# Adaptador_ESP12.net
KiCad netlist of a schematic drawn in EAGLE
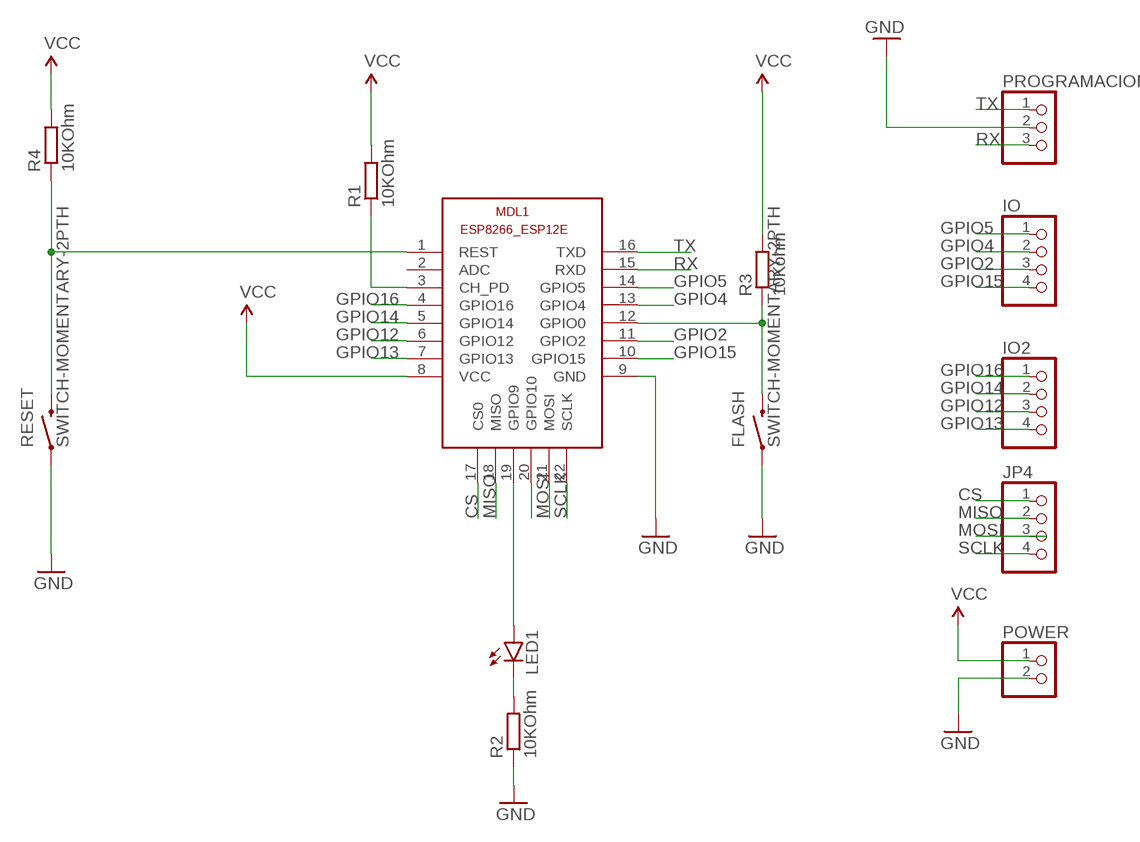
[diagram p0: schematic, sheet 1]

(export (version "E")
  (design (tool "Eeschema 10.0.6"))
  (components
    (comp (ref "FLASH")
      (value "SWITCH-MOMENTARY-2PTH")
      (footprint "eagle-import:TACTILE-PTH")
      (libsource (lib "eagle-import") (part "SWITCH-MOMENTARY-2PTH"))
    )
    (comp (ref "IO")
      (value "PINHD-1X4")
      (footprint "eagle-import:1X04")
      (libsource (lib "eagle-import") (part "PINHD-1X4"))
    )
    (comp (ref "IO2")
      (value "PINHD-1X4")
      (footprint "eagle-import:1X04")
      (libsource (lib "eagle-import") (part "PINHD-1X4"))
    )
    (comp (ref "JP4")
      (value "PINHD-1X4")
      (footprint "eagle-import:1X04")
      (libsource (lib "eagle-import") (part "PINHD-1X4"))
    )
    (comp (ref "LED1")
      (value "LED-3MM-NO_SILK")
      (footprint "eagle-import:LED3MM-NS")
      (libsource (lib "eagle-import") (part "LED-3MM-NO_SILK"))
    )
    (comp (ref "MDL1")
      (value "ESP8266-12EESP8266-ESP12E")
      (footprint "eagle-import:ESP8266-ESP12E")
      (libsource (lib "eagle-import") (part "ESP8266-12EESP8266-ESP12E"))
    )
    (comp (ref "POWER")
      (value "PINHD-1X2")
      (footprint "eagle-import:1X02")
      (libsource (lib "eagle-import") (part "PINHD-1X2"))
    )
    (comp (ref "PROGRAMACION")
      (value "PINHD-1X3")
      (footprint "eagle-import:1X03")
      (libsource (lib "eagle-import") (part "PINHD-1X3"))
    )
    (comp (ref "R1")
      (value "10KOhm")
      (footprint "eagle-import:0207_7")
      (libsource (lib "eagle-import") (part "R-EU_0207/7"))
    )
    (comp (ref "R2")
      (value "10KOhm")
      (footprint "eagle-import:0207_7")
      (libsource (lib "eagle-import") (part "R-EU_0207/7"))
    )
    (comp (ref "R3")
      (value "10Kohm")
      (footprint "eagle-import:0207_7")
      (libsource (lib "eagle-import") (part "R-EU_0207/7"))
    )
    (comp (ref "R4")
      (value "10KOhm")
      (footprint "eagle-import:0207_7")
      (libsource (lib "eagle-import") (part "R-EU_0207/7"))
    )
    (comp (ref "RESET")
      (value "SWITCH-MOMENTARY-2PTH")
      (footprint "eagle-import:TACTILE-PTH")
      (libsource (lib "eagle-import") (part "SWITCH-MOMENTARY-2PTH"))
    )
  )
  (nets
    (net (code "1") (name "/CS") (class "Default")
      (node (ref "JP4") (pin "1") (pinfunction "1_1") (pintype "passive"))
      (node (ref "MDL1") (pin "17") (pinfunction "CS0_17") (pintype "bidirectional"))
    )
    (net (code "2") (name "/GPIO2") (class "Default")
      (node (ref "IO") (pin "3") (pinfunction "3_3") (pintype "passive"))
      (node (ref "MDL1") (pin "11") (pinfunction "GPIO2_11") (pintype "bidirectional"))
    )
    (net (code "3") (name "/GPIO4") (class "Default")
      (node (ref "IO") (pin "2") (pinfunction "2_2") (pintype "passive"))
      (node (ref "MDL1") (pin "13") (pinfunction "GPIO4_13") (pintype "bidirectional"))
    )
    (net (code "4") (name "/GPIO5") (class "Default")
      (node (ref "IO") (pin "1") (pinfunction "1_1") (pintype "passive"))
      (node (ref "MDL1") (pin "14") (pinfunction "GPIO5_14") (pintype "bidirectional"))
    )
    (net (code "5") (name "/GPIO12") (class "Default")
      (node (ref "IO2") (pin "3") (pinfunction "3_3") (pintype "passive"))
      (node (ref "MDL1") (pin "6") (pinfunction "GPIO12_6") (pintype "bidirectional"))
    )
    (net (code "6") (name "/GPIO13") (class "Default")
      (node (ref "IO2") (pin "4") (pinfunction "4_4") (pintype "passive"))
      (node (ref "MDL1") (pin "7") (pinfunction "GPIO13_7") (pintype "bidirectional"))
    )
    (net (code "7") (name "/GPIO14") (class "Default")
      (node (ref "IO2") (pin "2") (pinfunction "2_2") (pintype "passive"))
      (node (ref "MDL1") (pin "5") (pinfunction "GPIO14_5") (pintype "bidirectional"))
    )
    (net (code "8") (name "/GPIO15") (class "Default")
      (node (ref "IO") (pin "4") (pinfunction "4_4") (pintype "passive"))
      (node (ref "MDL1") (pin "10") (pinfunction "GPIO15_10") (pintype "bidirectional"))
    )
    (net (code "9") (name "/GPIO16") (class "Default")
      (node (ref "IO2") (pin "1") (pinfunction "1_1") (pintype "passive"))
      (node (ref "MDL1") (pin "4") (pinfunction "GPIO16_4") (pintype "bidirectional"))
    )
    (net (code "10") (name "/MISO") (class "Default")
      (node (ref "JP4") (pin "2") (pinfunction "2_2") (pintype "passive"))
      (node (ref "MDL1") (pin "18") (pinfunction "MISO_18") (pintype "bidirectional"))
    )
    (net (code "11") (name "/MOSI") (class "Default")
      (node (ref "MDL1") (pin "21") (pinfunction "MOSI_21") (pintype "bidirectional"))
    )
    (net (code "12") (name "/RX") (class "Default")
      (node (ref "MDL1") (pin "15") (pinfunction "RXD_15") (pintype "bidirectional"))
      (node (ref "PROGRAMACION") (pin "3") (pinfunction "3_3") (pintype "passive"))
    )
    (net (code "13") (name "/SCLK") (class "Default")
      (node (ref "JP4") (pin "4") (pinfunction "4_4") (pintype "passive"))
      (node (ref "MDL1") (pin "22") (pinfunction "SCLK_22") (pintype "bidirectional"))
    )
    (net (code "14") (name "/TX") (class "Default")
      (node (ref "MDL1") (pin "16") (pinfunction "TXD_16") (pintype "bidirectional"))
      (node (ref "PROGRAMACION") (pin "1") (pinfunction "1_1") (pintype "passive"))
    )
    (net (code "15") (name "GND") (class "Default")
      (node (ref "FLASH") (pin "1") (pinfunction "1_1") (pintype "passive"))
      (node (ref "MDL1") (pin "9") (pinfunction "GND_9") (pintype "bidirectional"))
      (node (ref "POWER") (pin "2") (pinfunction "2_2") (pintype "passive"))
      (node (ref "PROGRAMACION") (pin "2") (pinfunction "2_2") (pintype "passive"))
      (node (ref "R2") (pin "1") (pinfunction "1_1") (pintype "passive"))
      (node (ref "RESET") (pin "1") (pinfunction "1_1") (pintype "passive"))
    )
    (net (code "16") (name "Net-(FLASH-2)") (class "Default")
      (node (ref "FLASH") (pin "3") (pinfunction "2_3") (pintype "passive"))
      (node (ref "MDL1") (pin "12") (pinfunction "GPIO0_12") (pintype "bidirectional"))
      (node (ref "R3") (pin "1") (pinfunction "1_1") (pintype "passive"))
    )
    (net (code "17") (name "Net-(LED1-C)") (class "Default")
      (node (ref "LED1") (pin "K") (pinfunction "C_K") (pintype "passive"))
      (node (ref "R2") (pin "2") (pinfunction "2_2") (pintype "passive"))
    )
    (net (code "18") (name "Net-(MDL1-CH_PD)") (class "Default")
      (node (ref "MDL1") (pin "3") (pinfunction "CH_PD_3") (pintype "bidirectional"))
      (node (ref "R1") (pin "1") (pinfunction "1_1") (pintype "passive"))
    )
    (net (code "19") (name "Net-(MDL1-GPIO9)") (class "Default")
      (node (ref "LED1") (pin "A") (pinfunction "A_A") (pintype "passive"))
      (node (ref "MDL1") (pin "19") (pinfunction "GPIO9_19") (pintype "bidirectional"))
    )
    (net (code "20") (name "Net-(MDL1-REST)") (class "Default")
      (node (ref "MDL1") (pin "1") (pinfunction "REST_1") (pintype "bidirectional"))
      (node (ref "R4") (pin "1") (pinfunction "1_1") (pintype "passive"))
      (node (ref "RESET") (pin "3") (pinfunction "2_3") (pintype "passive"))
    )
    (net (code "21") (name "VCC") (class "Default")
      (node (ref "MDL1") (pin "8") (pinfunction "VCC_8") (pintype "bidirectional"))
      (node (ref "POWER") (pin "1") (pinfunction "1_1") (pintype "passive"))
      (node (ref "R1") (pin "2") (pinfunction "2_2") (pintype "passive"))
      (node (ref "R3") (pin "2") (pinfunction "2_2") (pintype "passive"))
      (node (ref "R4") (pin "2") (pinfunction "2_2") (pintype "passive"))
    )
    (net (code "22") (name "unconnected-(JP4-Pad3)") (class "Default")
      (node (ref "JP4") (pin "3") (pinfunction "3_3") (pintype "passive"))
    )
    (net (code "23") (name "unconnected-(MDL1-ADC-Pad2)") (class "Default")
      (node (ref "MDL1") (pin "2") (pinfunction "ADC_2") (pintype "bidirectional"))
    )
    (net (code "24") (name "unconnected-(MDL1-GPIO10-Pad20)") (class "Default")
      (node (ref "MDL1") (pin "20") (pinfunction "GPIO10_20") (pintype "bidirectional"))
    )
  )
)
